# Teensylu-1_3a.net
KiCad netlist of a schematic drawn in EAGLE
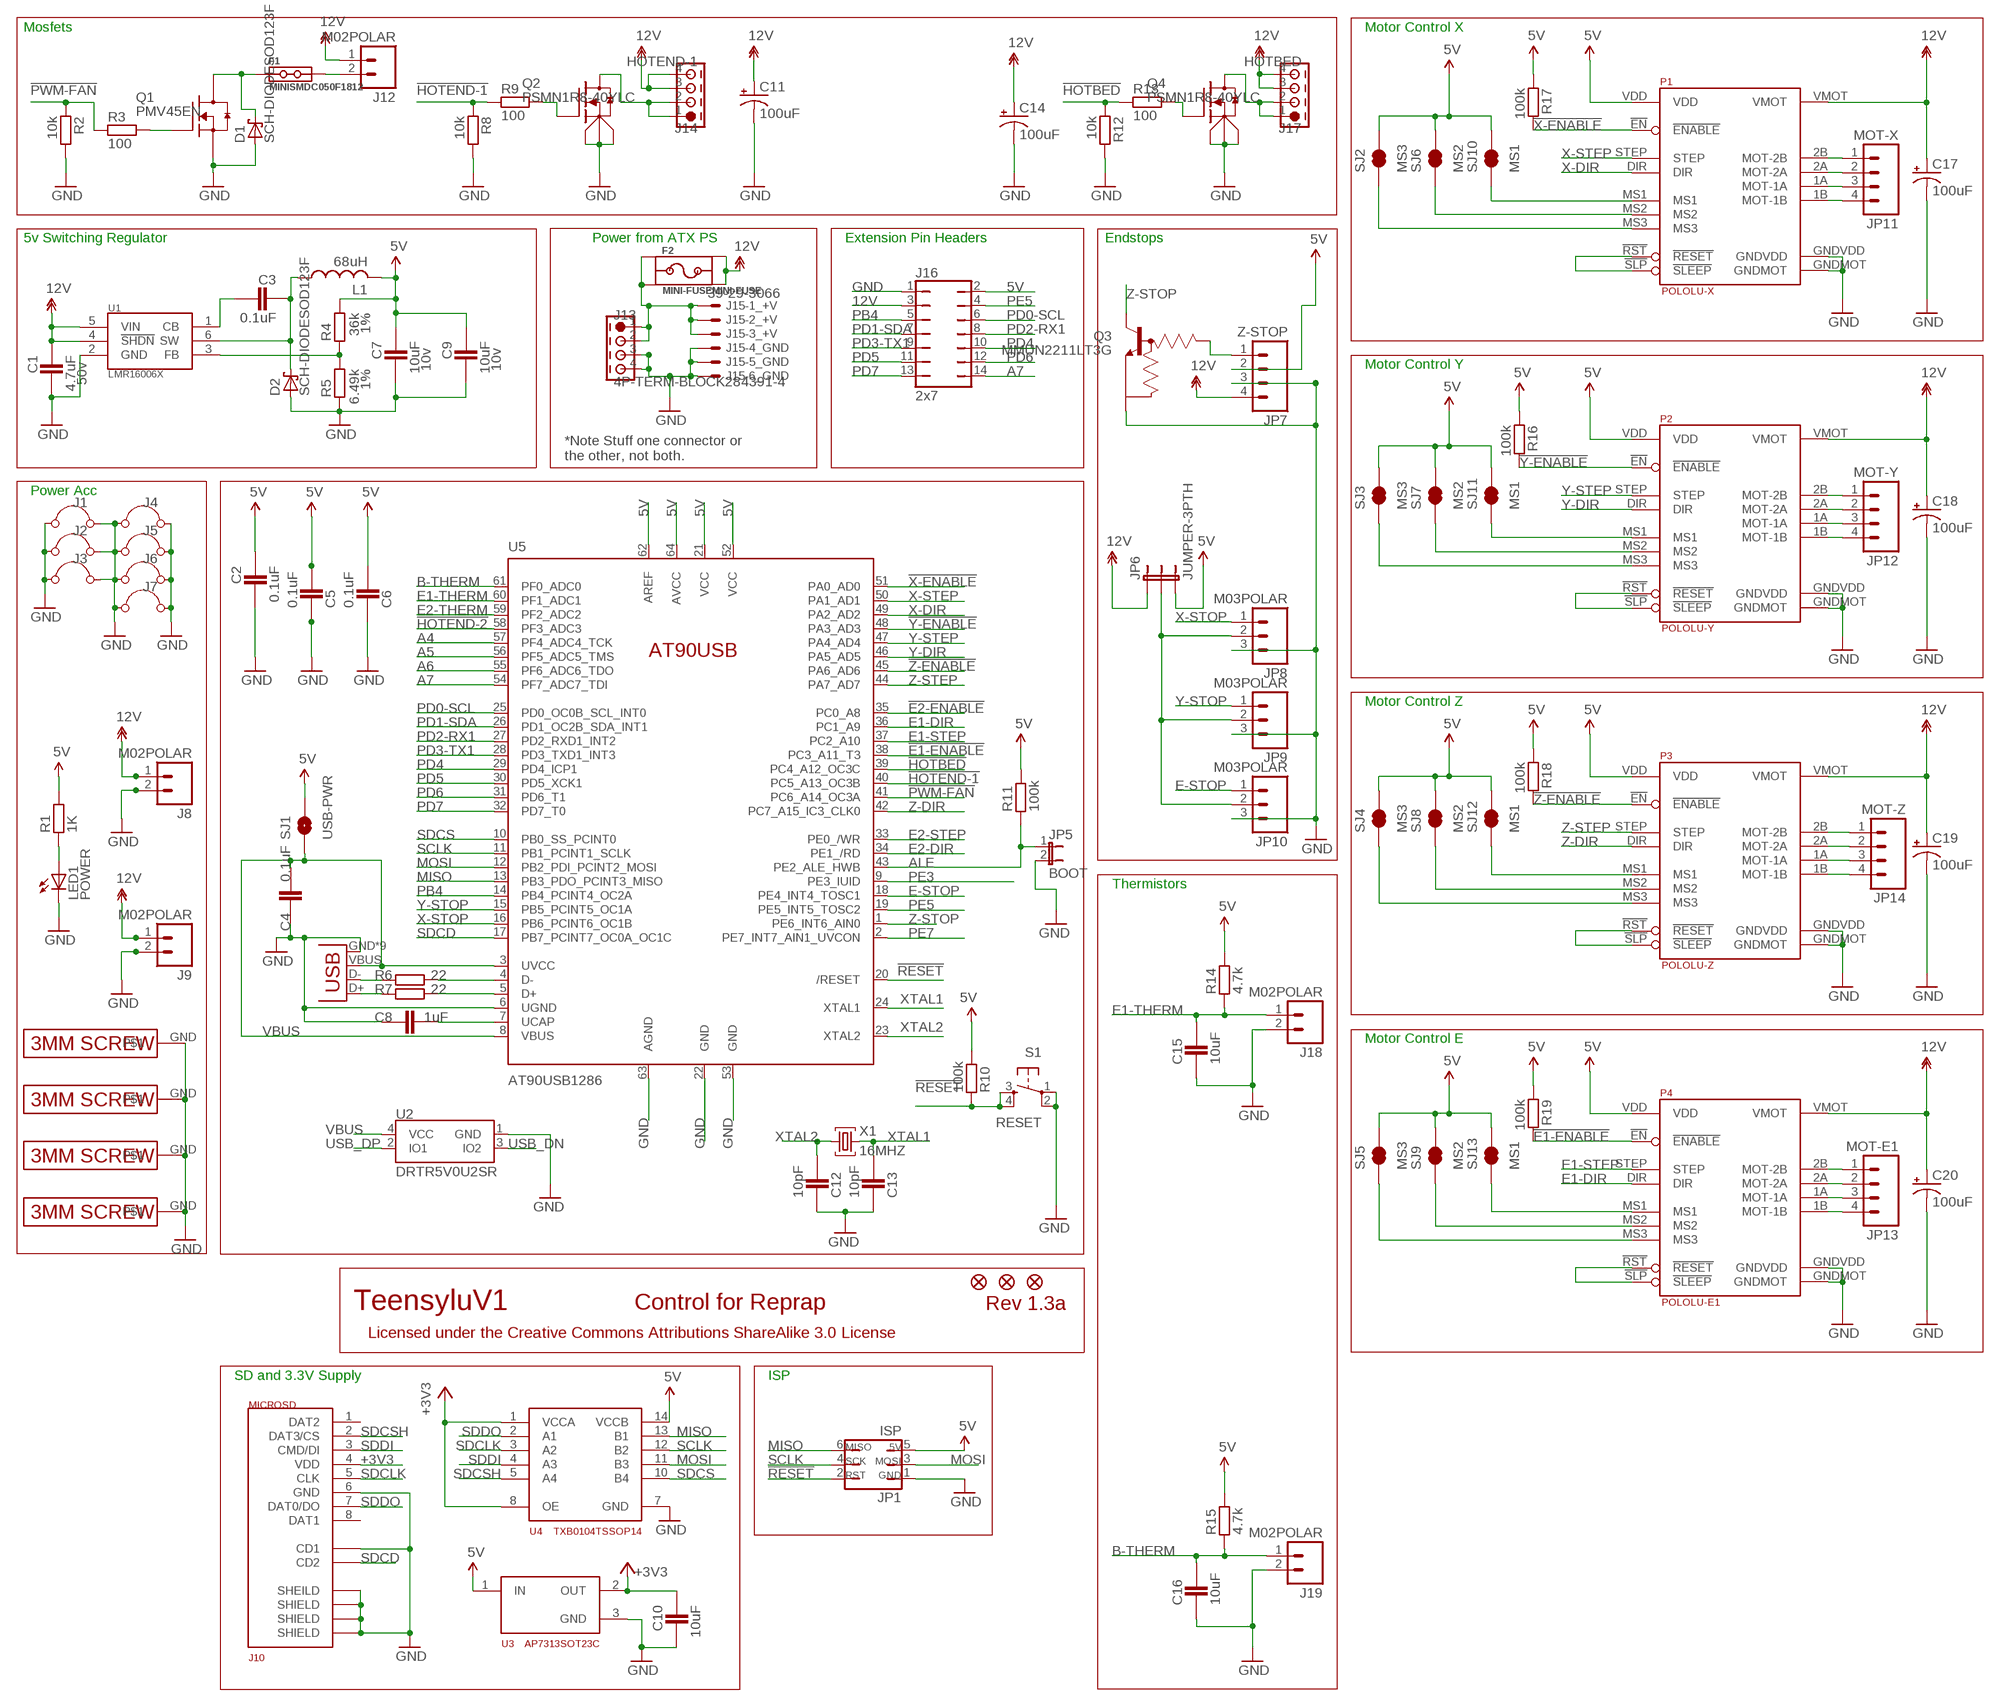
[diagram p0: schematic, sheet 1]

(export (version "E")
  (design (tool "Eeschema 10.0.6"))
  (components
    (comp (ref "C1")
      (value "4.7uF")
      (footprint "eagle-import:CAPC3215X168N")
      (fields
        (field (name "MANUFACTURER") "Yaiyo Yuden")
        (field (name "MANUFACTURER_PART_NUMBER") "UMK316AB7475KL-T")
        (field (name "TOLERANCE") "10%")
        (field (name "VDC") "50v")
      )
      (libsource (lib "eagle-import") (part "CAPACITOR_1206"))
    )
    (comp (ref "C2")
      (value "0.1uF")
      (footprint "eagle-import:CAPC1608X92N")
      (fields
        (field (name "MANUFACTURER") "Murata")
        (field (name "MANUFACTURER_PART_NUMBER") "GRM188R71C104KA01D")
        (field (name "TOLERANCE") "10%")
      )
      (libsource (lib "eagle-import") (part "CAPACITOR_0603"))
    )
    (comp (ref "C3")
      (value "0.1uF")
      (footprint "eagle-import:CAPC1608X92N")
      (fields
        (field (name "MANUFACTURER") "Samsung")
        (field (name "MANUFACTURER_PART_NUMBER") "CL10B104KB8NNNC")
        (field (name "TOLERANCE") "10%")
      )
      (libsource (lib "eagle-import") (part "CAPACITOR_0603"))
    )
    (comp (ref "C4")
      (value "0.1uF")
      (footprint "eagle-import:CAPC1608X92N")
      (fields
        (field (name "MANUFACTURER") "Murata")
        (field (name "MANUFACTURER_PART_NUMBER") "GRM188R71C104KA01D")
        (field (name "TOLERANCE") "10%")
      )
      (libsource (lib "eagle-import") (part "CAPACITOR_0603"))
    )
    (comp (ref "C5")
      (value "0.1uF")
      (footprint "eagle-import:CAPC1608X92N")
      (fields
        (field (name "MANUFACTURER") "Murata")
        (field (name "MANUFACTURER_PART_NUMBER") "GRM188R71C104KA01D")
        (field (name "TOLERANCE") "10%")
      )
      (libsource (lib "eagle-import") (part "CAPACITOR_0603"))
    )
    (comp (ref "C6")
      (value "0.1uF")
      (footprint "eagle-import:CAPC1608X92N")
      (fields
        (field (name "MANUFACTURER") "Murata")
        (field (name "MANUFACTURER_PART_NUMBER") "GRM188R71C104KA01D")
        (field (name "TOLERANCE") "10%")
      )
      (libsource (lib "eagle-import") (part "CAPACITOR_0603"))
    )
    (comp (ref "C7")
      (value "10uF")
      (footprint "eagle-import:CAPC2012X145AN")
      (fields
        (field (name "MANUFACTURER") "Murata")
        (field (name "MANUFACTURER_PART_NUMBER") "GRM21BR71A106KE51L")
        (field (name "TOLERANCE") "10%")
        (field (name "VDC") "10v")
      )
      (libsource (lib "eagle-import") (part "CAPACITOR_0805"))
    )
    (comp (ref "C8")
      (value "1uF")
      (footprint "eagle-import:CAPC1608X92N")
      (fields
        (field (name "MANUFACTURER") "Samsung")
        (field (name "MANUFACTURER_PART_NUMBER") "CL10A105MO8NNNC")
        (field (name "TOLERANCE") "20%")
      )
      (libsource (lib "eagle-import") (part "CAPACITOR_0603"))
    )
    (comp (ref "C9")
      (value "10uF")
      (footprint "eagle-import:CAPC2012X145AN")
      (fields
        (field (name "MANUFACTURER") "Murata")
        (field (name "MANUFACTURER_PART_NUMBER") "GRM21BR71A106KE51L")
        (field (name "TOLERANCE") "10%")
        (field (name "VDC") "10v")
      )
      (libsource (lib "eagle-import") (part "CAPACITOR_0805"))
    )
    (comp (ref "C10")
      (value "10uF")
      (footprint "eagle-import:CAPC1608X92N")
      (fields
        (field (name "MANUFACTURER") "Murata")
        (field (name "MANUFACTURER_PART_NUMBER") "GRM188R61C106MA73D")
        (field (name "TOLERANCE") "20%")
      )
      (libsource (lib "eagle-import") (part "CAPACITOR_0603"))
    )
    (comp (ref "C11")
      (value "100uF")
      (footprint "eagle-import:PANASONIC_D")
      (fields
        (field (name "MANUFACTURER") "Panasonic")
        (field (name "MANUFACTURER_PART_NUMBER") "EEE-FTH101XAP")
        (field (name "TOLERANCE") "20%")
      )
      (libsource (lib "eagle-import") (part "CPOL-USD"))
    )
    (comp (ref "C12")
      (value "10pF")
      (footprint "eagle-import:CAPC1608X92N")
      (fields
        (field (name "MANUFACTURER") "Samsung")
        (field (name "MANUFACTURER_PART_NUMBER") "CL10C100JB8NCNC")
        (field (name "TOLERANCE") "5%")
      )
      (libsource (lib "eagle-import") (part "CAPACITOR_0603"))
    )
    (comp (ref "C13")
      (value "10pF")
      (footprint "eagle-import:CAPC1608X92N")
      (fields
        (field (name "MANUFACTURER") "Samsung")
        (field (name "MANUFACTURER_PART_NUMBER") "CL10C100JB8NCNC")
        (field (name "TOLERANCE") "5%")
      )
      (libsource (lib "eagle-import") (part "CAPACITOR_0603"))
    )
    (comp (ref "C14")
      (value "100uF")
      (footprint "eagle-import:PANASONIC_D")
      (fields
        (field (name "MANUFACTURER") "Panasonic")
        (field (name "MANUFACTURER_PART_NUMBER") "EEE-FTH101XAP")
        (field (name "TOLERANCE") "20%")
      )
      (libsource (lib "eagle-import") (part "CPOL-USD"))
    )
    (comp (ref "C15")
      (value "10uF")
      (footprint "eagle-import:CAPC1608X92N")
      (fields
        (field (name "MANUFACTURER") "Murata")
        (field (name "MANUFACTURER_PART_NUMBER") "GRM188R61C106MA73D")
        (field (name "TOLERANCE") "20%")
      )
      (libsource (lib "eagle-import") (part "CAPACITOR_0603"))
    )
    (comp (ref "C16")
      (value "10uF")
      (footprint "eagle-import:CAPC1608X92N")
      (fields
        (field (name "MANUFACTURER") "Murata")
        (field (name "MANUFACTURER_PART_NUMBER") "GRM188R61C106MA73D")
        (field (name "TOLERANCE") "20%")
      )
      (libsource (lib "eagle-import") (part "CAPACITOR_0603"))
    )
    (comp (ref "C17")
      (value "100uF")
      (footprint "eagle-import:PANASONIC_D")
      (fields
        (field (name "MANUFACTURER") "Panasonic")
        (field (name "MANUFACTURER_PART_NUMBER") "EEE-FTH101XAP")
        (field (name "TOLERANCE") "20%")
      )
      (libsource (lib "eagle-import") (part "CPOL-USD"))
    )
    (comp (ref "C18")
      (value "100uF")
      (footprint "eagle-import:PANASONIC_D")
      (fields
        (field (name "MANUFACTURER") "Panasonic")
        (field (name "MANUFACTURER_PART_NUMBER") "EEE-FTH101XAP")
        (field (name "TOLERANCE") "20%")
      )
      (libsource (lib "eagle-import") (part "CPOL-USD"))
    )
    (comp (ref "C19")
      (value "100uF")
      (footprint "eagle-import:PANASONIC_D")
      (fields
        (field (name "MANUFACTURER") "Panasonic")
        (field (name "MANUFACTURER_PART_NUMBER") "EEE-FTH101XAP")
        (field (name "TOLERANCE") "20%")
      )
      (libsource (lib "eagle-import") (part "CPOL-USD"))
    )
    (comp (ref "C20")
      (value "100uF")
      (footprint "eagle-import:PANASONIC_D")
      (fields
        (field (name "MANUFACTURER") "Panasonic")
        (field (name "MANUFACTURER_PART_NUMBER") "EEE-FTH101XAP")
        (field (name "TOLERANCE") "20%")
      )
      (libsource (lib "eagle-import") (part "CPOL-USD"))
    )
    (comp (ref "D1")
      (value "SCH-DIODESOD123F")
      (footprint "eagle-import:SOD123F")
      (fields
        (field (name "MANUFACTURER") "NXP Semiconductors")
        (field (name "MANUFACTURER_PART_NUMBER") "PMEG4010CEH,115")
        (field (name "CURRENT") "1A")
        (field (name "MANUFACTURER_1") "NXP Semiconductors")
      )
      (libsource (lib "eagle-import") (part "SCH-DIODESOD123F"))
    )
    (comp (ref "D2")
      (value "SCH-DIODESOD123F")
      (footprint "eagle-import:SOD123F")
      (fields
        (field (name "MANUFACTURER") "NXP Semiconductors")
        (field (name "MANUFACTURER_PART_NUMBER") "PMEG4010CEH,115")
        (field (name "CURRENT") "1A")
        (field (name "MANUFACTURER_1") "NXP Semiconductors")
        (field (name "MANUFACTURER_PART_NUMBER_1") "PMEG4010CEH,115")
        (field (name "REVERSE_VOLTAGE") "40V")
      )
      (libsource (lib "eagle-import") (part "SCH-DIODESOD123F"))
    )
    (comp (ref "F1")
      (value "MINISMDC050F1812")
      (footprint "eagle-import:MINISMDC")
      (fields
        (field (name "MANUFACTURER") "TE Connectivity")
        (field (name "MANUFACTURER_PART_NUMBER") "MINISMDC050F-2")
      )
      (libsource (lib "eagle-import") (part "MINISMDC050F1812"))
    )
    (comp (ref "F2")
      (value "MINI-FUSEMINI-FUSE")
      (footprint "eagle-import:MINI_FUSE")
      (fields (field (name "MANUFACTURER") "Keystone") (field (name "MANUFACTURER_PART_NUMBER") "3568"))
      (libsource (lib "eagle-import") (part "MINI-FUSEMINI-FUSE"))
    )
    (comp (ref "J1")
      (value "22ga")
      (footprint "eagle-import:WJ_01_08")
      (description "22ga jumper wire")
      (libsource (lib "eagle-import") (part "WIRE_JUMPER-0.1"))
    )
    (comp (ref "J2")
      (value "22ga")
      (footprint "eagle-import:WJ_01_08")
      (description "22ga jumper wire")
      (libsource (lib "eagle-import") (part "WIRE_JUMPER-0.1"))
    )
    (comp (ref "J3")
      (value "22ga")
      (footprint "eagle-import:WJ_01_08")
      (description "22ga jumper wire")
      (libsource (lib "eagle-import") (part "WIRE_JUMPER-0.1"))
    )
    (comp (ref "J4")
      (value "22ga")
      (footprint "eagle-import:WJ_01_08")
      (description "22ga jumper wire")
      (libsource (lib "eagle-import") (part "WIRE_JUMPER-0.1"))
    )
    (comp (ref "J5")
      (value "22ga")
      (footprint "eagle-import:WJ_01_08")
      (description "22ga jumper wire")
      (libsource (lib "eagle-import") (part "WIRE_JUMPER-0.1"))
    )
    (comp (ref "J6")
      (value "22ga")
      (footprint "eagle-import:WJ_01_08")
      (description "22ga jumper wire")
      (libsource (lib "eagle-import") (part "WIRE_JUMPER-0.1"))
    )
    (comp (ref "J7")
      (value "22ga")
      (footprint "eagle-import:WJ_01_08")
      (description "22ga jumper wire")
      (libsource (lib "eagle-import") (part "WIRE_JUMPER-0.1"))
    )
    (comp (ref "J8")
      (value "M02POLAR")
      (footprint "eagle-import:MOLEX-1X2")
      (description "CONN HEADER 2POS .100 VERT TIN")
      (fields (field (name "MANUFACTURER") "Molex") (field (name "MANUFACTURER_PART_NUMBER") "0022272021"))
      (libsource (lib "eagle-import") (part "M02POLAR"))
    )
    (comp (ref "J9")
      (value "M02POLAR")
      (footprint "eagle-import:MOLEX-1X2")
      (description "CONN HEADER 2POS .100 VERT TIN")
      (fields (field (name "MANUFACTURER") "Molex") (field (name "MANUFACTURER_PART_NUMBER") "0022272021"))
      (libsource (lib "eagle-import") (part "M02POLAR"))
    )
    (comp (ref "J10")
      (value "MICROSD")
      (footprint "eagle-import:AMPHENOL-MICROSD")
      (description "CONN MICRO SD CARD PUSH-PULL R/A")
      (fields
        (field (name "MANUFACTURER") "Amphenol")
        (field (name "MANUFACTURER_PART_NUMBER") "114-00841-68")
      )
      (libsource (lib "eagle-import") (part "MICROSD"))
    )
    (comp (ref "J11")
      (value "USB-MICRO-PTH")
      (footprint "eagle-import:USB-MICROB-PTH")
      (fields (field (name "MANUFACTURER") "FCI") (field (name "MANUFACTURER_PART_NUMBER") "10118194-0001LF"))
      (libsource (lib "eagle-import") (part "USB-MICRO-PTH"))
    )
    (comp (ref "J12")
      (value "M02POLAR")
      (footprint "eagle-import:MOLEX-1X2")
      (description "CONN HEADER 2POS .100 VERT TIN")
      (fields (field (name "MANUFACTURER") "Molex") (field (name "MANUFACTURER_PART_NUMBER") "0022272021"))
      (libsource (lib "eagle-import") (part "M02POLAR"))
    )
    (comp (ref "J13")
      (value "4P-TERM-BLOCK284391-4")
      (footprint "eagle-import:284391-4")
      (fields
        (field (name "MANUFACTURER") "TE Connectivity")
        (field (name "MANUFACTURER_PART_NUMBER") "284391-4")
      )
      (libsource (lib "eagle-import") (part "4P-TERM-BLOCK284391-4"))
    )
    (comp (ref "J14")
      (value "HOTEND-1")
      (footprint "eagle-import:284391-4")
      (fields
        (field (name "MANUFACTURER") "TE Connectivity")
        (field (name "MANUFACTURER_PART_NUMBER") "284391-4")
      )
      (libsource (lib "eagle-import") (part "4P-TERM-BLOCK284391-4"))
    )
    (comp (ref "J15")
      (value "39-29-3066")
      (footprint "eagle-import:39-29-3066")
      (fields (field (name "MANUFACTURER") "Molex") (field (name "MANUFACTURER_PART_NUMBER") "0039293066"))
      (libsource (lib "eagle-import") (part "39-29-3066"))
    )
    (comp (ref "J16")
      (value "2x7")
      (footprint "eagle-import:JP7Q")
      (description "DIL VERTICAL PC TAIL PIN HEADER")
      (fields (field (name "MANUFACTURER") "Harwin") (field (name "MANUFACTURER_PART_NUMBER") "M20-9980746"))
      (libsource (lib "eagle-import") (part "JP7Q"))
    )
    (comp (ref "J17")
      (value "HOTBED")
      (footprint "eagle-import:284391-4")
      (fields
        (field (name "MANUFACTURER") "TE Connectivity")
        (field (name "MANUFACTURER_PART_NUMBER") "284391-4")
      )
      (libsource (lib "eagle-import") (part "4P-TERM-BLOCK284391-4"))
    )
    (comp (ref "J18")
      (value "M02POLAR")
      (footprint "eagle-import:MOLEX-1X2")
      (description "CONN HEADER 2POS .100 VERT TIN")
      (fields (field (name "MANUFACTURER") "Molex") (field (name "MANUFACTURER_PART_NUMBER") "0022272021"))
      (libsource (lib "eagle-import") (part "M02POLAR"))
    )
    (comp (ref "J19")
      (value "M02POLAR")
      (footprint "eagle-import:MOLEX-1X2")
      (description "CONN HEADER 2POS .100 VERT TIN")
      (fields (field (name "MANUFACTURER") "Molex") (field (name "MANUFACTURER_PART_NUMBER") "0022272021"))
      (libsource (lib "eagle-import") (part "M02POLAR"))
    )
    (comp (ref "JP1")
      (value "ISP")
      (footprint "eagle-import:ISP")
      (libsource (lib "eagle-import") (part "PROGHEADER"))
    )
    (comp (ref "JP2")
      (value "FIDUCIAL1X2.5")
      (footprint "eagle-import:FIDUCIAL-1X2.5")
      (libsource (lib "eagle-import") (part "FIDUCIAL1X2.5"))
    )
    (comp (ref "JP3")
      (value "FIDUCIAL1X2.5")
      (footprint "eagle-import:FIDUCIAL-1X2.5")
      (libsource (lib "eagle-import") (part "FIDUCIAL1X2.5"))
    )
    (comp (ref "JP4")
      (value "FIDUCIAL1X2.5")
      (footprint "eagle-import:FIDUCIAL-1X2.5")
      (libsource (lib "eagle-import") (part "FIDUCIAL1X2.5"))
    )
    (comp (ref "JP5")
      (value "BOOT")
      (footprint "eagle-import:1X02")
      (description "SIL VERTICAL PC TAIL PIN HEADER")
      (fields (field (name "MANUFACTURER") "Harwin") (field (name "MANUFACTURER_PART_NUMBER") "M20-9990246"))
      (libsource (lib "eagle-import") (part "JUMPER-2PTH"))
    )
    (comp (ref "JP6")
      (value "JUMPER-3PTH")
      (footprint "eagle-import:1X03")
      (libsource (lib "eagle-import") (part "JUMPER-3PTH"))
    )
    (comp (ref "JP7")
      (value "Z-STOP")
      (footprint "eagle-import:MOLEX-1X4")
      (fields (field (name "MANUFACTURER") "Molex") (field (name "MANUFACTURER_PART_NUMBER") "0022272041"))
      (libsource (lib "eagle-import") (part "M04POLAR"))
    )
    (comp (ref "JP8")
      (value "M03POLAR")
      (footprint "eagle-import:MOLEX-1X3")
      (description "CONN HEADER 3POS .100 VERT TIN")
      (fields (field (name "MANUFACTURER") "Molex") (field (name "MANUFACTURER_PART_NUMBER") "0022272031"))
      (libsource (lib "eagle-import") (part "M03POLAR"))
    )
    (comp (ref "JP9")
      (value "M03POLAR")
      (footprint "eagle-import:MOLEX-1X3")
      (description "CONN HEADER 3POS .100 VERT TIN")
      (fields (field (name "MANUFACTURER") "Molex") (field (name "MANUFACTURER_PART_NUMBER") "0022272031"))
      (libsource (lib "eagle-import") (part "M03POLAR"))
    )
    (comp (ref "JP10")
      (value "M03POLAR")
      (footprint "eagle-import:MOLEX-1X3")
      (description "CONN HEADER 3POS .100 VERT TIN")
      (fields (field (name "MANUFACTURER") "Molex") (field (name "MANUFACTURER_PART_NUMBER") "0022272031"))
      (libsource (lib "eagle-import") (part "M03POLAR"))
    )
    (comp (ref "JP11")
      (value "MOT-X")
      (footprint "eagle-import:MOLEX-1X4")
      (fields (field (name "MANUFACTURER") "Molex") (field (name "MANUFACTURER_PART_NUMBER") "0022272041"))
      (libsource (lib "eagle-import") (part "M04POLAR"))
    )
    (comp (ref "JP12")
      (value "MOT-Y")
      (footprint "eagle-import:MOLEX-1X4")
      (fields (field (name "MANUFACTURER") "Molex") (field (name "MANUFACTURER_PART_NUMBER") "0022272041"))
      (libsource (lib "eagle-import") (part "M04POLAR"))
    )
    (comp (ref "JP13")
      (value "MOT-E1")
      (footprint "eagle-import:MOLEX-1X4")
      (fields (field (name "MANUFACTURER") "Molex") (field (name "MANUFACTURER_PART_NUMBER") "0022272041"))
      (libsource (lib "eagle-import") (part "M04POLAR"))
    )
    (comp (ref "JP14")
      (value "MOT-Z")
      (footprint "eagle-import:MOLEX-1X4")
      (fields (field (name "MANUFACTURER") "Molex") (field (name "MANUFACTURER_PART_NUMBER") "0022272041"))
      (libsource (lib "eagle-import") (part "M04POLAR"))
    )
    (comp (ref "L1")
      (value "68uH")
      (footprint "eagle-import:SRN6045")
      (fields
        (field (name "MANUFACTURER") "Bourns")
        (field (name "MANUFACTURER_PART_NUMBER") "SRN6045-680M")
        (field (name "MANUFACTURER_1") "Bourns")
        (field (name "MANUFACTURER_PART_NUMBER_1") "SRN6045-680M")
      )
      (libsource (lib "eagle-import") (part "INDUCTORSRN6045"))
    )
    (comp (ref "LED1")
      (value "POWER")
      (footprint "eagle-import:CHIPLED_0805")
      (fields
        (field (name "MANUFACTURER") "Kingbright")
        (field (name "MANUFACTURER_PART_NUMBER") "APT2012SGC")
      )
      (libsource (lib "eagle-import") (part "LEDCHIPLED_0805"))
    )
    (comp (ref "P1")
      (value "POLOLU-X")
      (footprint "eagle-import:POLOLU-STEPPER-PTH")
      (libsource (lib "eagle-import") (part "POLOLU-ALLEGRO"))
    )
    (comp (ref "P2")
      (value "POLOLU-Y")
      (footprint "eagle-import:POLOLU-STEPPER-PTH")
      (libsource (lib "eagle-import") (part "POLOLU-ALLEGRO"))
    )
    (comp (ref "P3")
      (value "POLOLU-Z")
      (footprint "eagle-import:POLOLU-STEPPER-PTH")
      (libsource (lib "eagle-import") (part "POLOLU-ALLEGRO"))
    )
    (comp (ref "P4")
      (value "POLOLU-E1")
      (footprint "eagle-import:POLOLU-STEPPER-PTH")
      (libsource (lib "eagle-import") (part "POLOLU-ALLEGRO"))
    )
    (comp (ref "Q1")
      (value "PMV45EN")
      (footprint "eagle-import:SOT23C")
      (fields
        (field (name "MANUFACTURER") "International Rectifier")
        (field (name "MANUFACTURER_PART_NUMBER") "IRLML2060TRPBF")
        (field (name "VOLTAGE") "60V")
      )
      (libsource (lib "eagle-import") (part "MOSFET-NCH_SOT-23"))
    )
    (comp (ref "Q2")
      (value "PSMN1R8-40YLC")
      (footprint "eagle-import:LFPACK-POWERPAK-SO8")
      (fields
        (field (name "MANUFACTURER") "NXP Semiconductors")
        (field (name "MANUFACTURER_PART_NUMBER") "PSMN1R8-40YLC,115")
        (field (name "VOLTAGE") "40V")
      )
      (libsource (lib "eagle-import") (part "PSMN1R8-40YLCPOWERPACK-S08"))
    )
    (comp (ref "Q3")
      (value "MMUN2211LT3G")
      (footprint "eagle-import:SOT23C")
      (description "TRANS PREBIAS NPN 246MW SOT23-3")
      (fields (field (name "MANUFACTURER") "ON Semiconductor"))
      (libsource (lib "eagle-import") (part "TRANSISTOR_NPN_BIASSOT23C"))
    )
    (comp (ref "Q4")
      (value "PSMN1R8-40YLC")
      (footprint "eagle-import:LFPACK-POWERPAK-SO8")
      (fields
        (field (name "MANUFACTURER") "NXP Semiconductors")
        (field (name "MANUFACTURER_PART_NUMBER") "PSMN1R8-40YLC,115")
        (field (name "VOLTAGE") "40V")
      )
      (libsource (lib "eagle-import") (part "PSMN1R8-40YLCPOWERPACK-S08"))
    )
    (comp (ref "R1")
      (value "1K")
      (footprint "eagle-import:RESC1608X55N")
      (libsource (lib "eagle-import") (part "RESISTOR_0603"))
    )
    (comp (ref "R2")
      (value "10k")
      (footprint "eagle-import:RESC1608X55N")
      (libsource (lib "eagle-import") (part "RESISTOR_0603"))
    )
    (comp (ref "R3")
      (value "100")
      (footprint "eagle-import:RESC1608X55N")
      (libsource (lib "eagle-import") (part "RESISTOR_0603"))
    )
    (comp (ref "R4")
      (value "36k")
      (footprint "eagle-import:RESC1608X55N")
      (fields (field (name "TOLERANCE") "1%"))
      (libsource (lib "eagle-import") (part "RESISTOR_0603"))
    )
    (comp (ref "R5")
      (value "6.49k")
      (footprint "eagle-import:RESC1608X55N")
      (fields (field (name "TOLERANCE") "1%"))
      (libsource (lib "eagle-import") (part "RESISTOR_0603"))
    )
    (comp (ref "R6")
      (value "22")
      (footprint "eagle-import:RESC1608X55N")
      (libsource (lib "eagle-import") (part "RESISTOR_0603"))
    )
    (comp (ref "R7")
      (value "22")
      (footprint "eagle-import:RESC1608X55N")
      (libsource (lib "eagle-import") (part "RESISTOR_0603"))
    )
    (comp (ref "R8")
      (value "10k")
      (footprint "eagle-import:RESC1608X55N")
      (libsource (lib "eagle-import") (part "RESISTOR_0603"))
    )
    (comp (ref "R9")
      (value "100")
      (footprint "eagle-import:RESC1608X55N")
      (libsource (lib "eagle-import") (part "RESISTOR_0603"))
    )
    (comp (ref "R10")
      (value "100k")
      (footprint "eagle-import:RESC1608X55N")
      (libsource (lib "eagle-import") (part "RESISTOR_0603"))
    )
    (comp (ref "R11")
      (value "100k")
      (footprint "eagle-import:RESC1608X55N")
      (libsource (lib "eagle-import") (part "RESISTOR_0603"))
    )
    (comp (ref "R12")
      (value "10k")
      (footprint "eagle-import:RESC1608X55N")
      (libsource (lib "eagle-import") (part "RESISTOR_0603"))
    )
    (comp (ref "R13")
      (value "100")
      (footprint "eagle-import:RESC1608X55N")
      (libsource (lib "eagle-import") (part "RESISTOR_0603"))
    )
    (comp (ref "R14")
      (value "4.7k")
      (footprint "eagle-import:RESC1608X55N")
      (libsource (lib "eagle-import") (part "RESISTOR_0603"))
    )
    (comp (ref "R15")
      (value "4.7k")
      (footprint "eagle-import:RESC1608X55N")
      (libsource (lib "eagle-import") (part "RESISTOR_0603"))
    )
    (comp (ref "R16")
      (value "100k")
      (footprint "eagle-import:RESC1608X55N")
      (libsource (lib "eagle-import") (part "RESISTOR_0603"))
    )
    (comp (ref "R17")
      (value "100k")
      (footprint "eagle-import:RESC1608X55N")
      (libsource (lib "eagle-import") (part "RESISTOR_0603"))
    )
    (comp (ref "R18")
      (value "100k")
      (footprint "eagle-import:RESC1608X55N")
      (libsource (lib "eagle-import") (part "RESISTOR_0603"))
    )
    (comp (ref "R19")
      (value "100k")
      (footprint "eagle-import:RESC1608X55N")
      (libsource (lib "eagle-import") (part "RESISTOR_0603"))
    )
    (comp (ref "S1")
      (value "RESET")
      (footprint "eagle-import:TACTILE_SWITCH_SMD")
      (fields (field (name "MANUFACTURER") "Bourns") (field (name "MANUFACTURER_PART_NUMBER") "7914J-1-000E"))
      (libsource (lib "eagle-import") (part "TAC_SWITCHSMD"))
    )
    (comp (ref "SCREW1")
      (value "3MM-SCREW")
      (footprint "eagle-import:PLATEDSCREW")
      (libsource (lib "eagle-import") (part "3MM-SCREW"))
    )
    (comp (ref "SCREW2")
      (value "3MM-SCREW")
      (footprint "eagle-import:PLATEDSCREW")
      (libsource (lib "eagle-import") (part "3MM-SCREW"))
    )
    (comp (ref "SCREW3")
      (value "3MM-SCREW")
      (footprint "eagle-import:PLATEDSCREW")
      (libsource (lib "eagle-import") (part "3MM-SCREW"))
    )
    (comp (ref "SCREW4")
      (value "3MM-SCREW")
      (footprint "eagle-import:PLATEDSCREW")
      (libsource (lib "eagle-import") (part "3MM-SCREW"))
    )
    (comp (ref "SJ1")
      (value "USB-PWR")
      (footprint "eagle-import:SJ_2S-NO")
      (libsource (lib "eagle-import") (part "SOLDERJUMPERNO"))
    )
    (comp (ref "SJ2")
      (value "MS3")
      (footprint "eagle-import:SJ_2S-TRACE")
      (libsource (lib "eagle-import") (part "SOLDERJUMPER-NCSJ-TRACE"))
    )
    (comp (ref "SJ3")
      (value "MS3")
      (footprint "eagle-import:SJ_2S-TRACE")
      (libsource (lib "eagle-import") (part "SOLDERJUMPER-NCSJ-TRACE"))
    )
    (comp (ref "SJ4")
      (value "MS3")
      (footprint "eagle-import:SJ_2S-TRACE")
      (libsource (lib "eagle-import") (part "SOLDERJUMPER-NCSJ-TRACE"))
    )
    (comp (ref "SJ5")
      (value "MS3")
      (footprint "eagle-import:SJ_2S-TRACE")
      (libsource (lib "eagle-import") (part "SOLDERJUMPER-NCSJ-TRACE"))
    )
    (comp (ref "SJ6")
      (value "MS2")
      (footprint "eagle-import:SJ_2S-TRACE")
      (libsource (lib "eagle-import") (part "SOLDERJUMPER-NCSJ-TRACE"))
    )
    (comp (ref "SJ7")
      (value "MS2")
      (footprint "eagle-import:SJ_2S-TRACE")
      (libsource (lib "eagle-import") (part "SOLDERJUMPER-NCSJ-TRACE"))
    )
    (comp (ref "SJ8")
      (value "MS2")
      (footprint "eagle-import:SJ_2S-TRACE")
      (libsource (lib "eagle-import") (part "SOLDERJUMPER-NCSJ-TRACE"))
    )
    (comp (ref "SJ9")
      (value "MS2")
      (footprint "eagle-import:SJ_2S-TRACE")
      (libsource (lib "eagle-import") (part "SOLDERJUMPER-NCSJ-TRACE"))
    )
    (comp (ref "SJ10")
      (value "MS1")
      (footprint "eagle-import:SJ_2S-TRACE")
      (libsource (lib "eagle-import") (part "SOLDERJUMPER-NCSJ-TRACE"))
    )
    (comp (ref "SJ11")
      (value "MS1")
      (footprint "eagle-import:SJ_2S-TRACE")
      (libsource (lib "eagle-import") (part "SOLDERJUMPER-NCSJ-TRACE"))
    )
    (comp (ref "SJ12")
      (value "MS1")
      (footprint "eagle-import:SJ_2S-TRACE")
      (libsource (lib "eagle-import") (part "SOLDERJUMPER-NCSJ-TRACE"))
    )
    (comp (ref "SJ13")
      (value "MS1")
      (footprint "eagle-import:SJ_2S-TRACE")
      (libsource (lib "eagle-import") (part "SOLDERJUMPER-NCSJ-TRACE"))
    )
    (comp (ref "U1")
      (value "LMR16006X")
      (footprint "eagle-import:TSOT6")
      (fields
        (field (name "MANUFACTURER") "Texas Instruments")
        (field (name "MANUFACTURER_PART_NUMBER") "LMR16006XDDCT")
      )
      (libsource (lib "eagle-import") (part "LMR16006X"))
    )
    (comp (ref "U2")
      (value "DRTR5V0U2SR")
      (footprint "eagle-import:SOT143-R")
      (fields
        (field (name "MANUFACTURER") "Diodes Incorporated")
        (field (name "MANUFACTURER_PART_NUMBER") "DTR5V0U2SR")
      )
      (libsource (lib "eagle-import") (part "DRTR5V0U2SR"))
    )
    (comp (ref "U3")
      (value "AP7313SOT23C")
      (footprint "eagle-import:SOT23C")
      (description "IC REG LDO 3.3V 0.15A SOT23-3")
      (fields
        (field (name "MANUFACTURER") "Diodes Incorporated")
        (field (name "MANUFACTURER_PART_NUMBER") "AP7313-33SAG-7")
      )
      (libsource (lib "eagle-import") (part "AP7313SOT23C"))
    )
    (comp (ref "U4")
      (value "TXB0104TSSOP14")
      (footprint "eagle-import:TSSOP14")
      (description "IC VOLT-LEVEL TRANSLATOR 14TSSOP")
      (fields
        (field (name "MANUFACTURER") "Texas Instruments")
        (field (name "MANUFACTURER_PART_NUMBER") "TXB0104PWR")
      )
      (libsource (lib "eagle-import") (part "TXB0104TSSOP14"))
    )
    (comp (ref "U5")
      (value "AT90USB1286")
      (footprint "eagle-import:TQFP64-2")
      (fields (field (name "MANUFACTURER") "Atmel"))
      (libsource (lib "eagle-import") (part "AT90USB"))
    )
    (comp (ref "X1")
      (value "16MHZ")
      (footprint "eagle-import:NDK-XTAL")
      (fields
        (field (name "MANUFACTURER") "NDK")
        (field (name "MANUFACTURER_PART_NUMBER") "NX5032GA-16.000000MHZ-LN-CD-1")
      )
      (libsource (lib "eagle-import") (part "XTAL"))
    )
  )
  (nets
    (net (code "1") (name "+3V3") (class "Default")
      (node (ref "C10") (pin "1") (pinfunction "1_1") (pintype "passive"))
      (node (ref "J10") (pin "4") (pinfunction "VDD_4") (pintype "power_in"))
      (node (ref "U3") (pin "2") (pinfunction "OUT_2") (pintype "power_in"))
      (node (ref "U4") (pin "1") (pinfunction "VCCA_1") (pintype "power_in"))
      (node (ref "U4") (pin "8") (pinfunction "OE_8") (pintype "input"))
    )
    (net (code "2") (name "/A4") (class "Default")
      (node (ref "U5") (pin "57") (pinfunction "PF4_ADC4_TCK_57") (pintype "bidirectional"))
    )
    (net (code "3") (name "/A5") (class "Default")
      (node (ref "U5") (pin "56") (pinfunction "PF5_ADC5_TMS_56") (pintype "bidirectional"))
    )
    (net (code "4") (name "/A6") (class "Default")
      (node (ref "U5") (pin "55") (pinfunction "PF6_ADC6_TDO_55") (pintype "bidirectional"))
    )
    (net (code "5") (name "/A7") (class "Default")
      (node (ref "J16") (pin "14") (pinfunction "14_14") (pintype "passive"))
      (node (ref "U5") (pin "54") (pinfunction "PF7_ADC7_TDI_54") (pintype "bidirectional"))
    )
    (net (code "6") (name "/ALE") (class "Default")
      (node (ref "JP5") (pin "1") (pinfunction "1_1") (pintype "passive"))
      (node (ref "R11") (pin "1") (pinfunction "1_1") (pintype "passive"))
      (node (ref "U5") (pin "43") (pinfunction "PE2_ALE_HWB_43") (pintype "bidirectional"))
    )
    (net (code "7") (name "/B-THERM") (class "Default")
      (node (ref "C16") (pin "2") (pinfunction "2_2") (pintype "passive"))
      (node (ref "J19") (pin "1") (pinfunction "1_1") (pintype "passive"))
      (node (ref "R15") (pin "1") (pinfunction "1_1") (pintype "passive"))
      (node (ref "U5") (pin "61") (pinfunction "PF0_ADC0_61") (pintype "bidirectional"))
    )
    (net (code "8") (name "/E-STOP") (class "Default")
      (node (ref "JP10") (pin "1") (pinfunction "1_1") (pintype "passive"))
      (node (ref "U5") (pin "18") (pinfunction "PE4_INT4_TOSC1_18") (pintype "bidirectional"))
    )
    (net (code "9") (name "/E1-DIR") (class "Default")
      (node (ref "P4") (pin "DIR") (pinfunction "DIR_DIR") (pintype "bidirectional"))
      (node (ref "U5") (pin "36") (pinfunction "PC1_A9_36") (pintype "bidirectional"))
    )
    (net (code "10") (name "/E1-STEP") (class "Default")
      (node (ref "P4") (pin "STEP") (pinfunction "STEP_STEP") (pintype "bidirectional"))
      (node (ref "U5") (pin "37") (pinfunction "PC2_A10_37") (pintype "bidirectional"))
    )
    (net (code "11") (name "/E1-THERM") (class "Default")
      (node (ref "C15") (pin "2") (pinfunction "2_2") (pintype "passive"))
      (node (ref "J18") (pin "1") (pinfunction "1_1") (pintype "passive"))
      (node (ref "R14") (pin "1") (pinfunction "1_1") (pintype "passive"))
      (node (ref "U5") (pin "60") (pinfunction "PF1_ADC1_60") (pintype "bidirectional"))
    )
    (net (code "12") (name "/E2-DIR") (class "Default")
      (node (ref "U5") (pin "34") (pinfunction "PE1_/RD_34") (pintype "bidirectional"))
    )
    (net (code "13") (name "/E2-STEP") (class "Default")
      (node (ref "U5") (pin "33") (pinfunction "PE0_/WR_33") (pintype "bidirectional"))
    )
    (net (code "14") (name "/E2-THERM") (class "Default")
      (node (ref "U5") (pin "59") (pinfunction "PF2_ADC2_59") (pintype "bidirectional"))
    )
    (net (code "15") (name "/MISO") (class "Default")
      (node (ref "JP1") (pin "6") (pinfunction "6_6") (pintype "passive"))
      (node (ref "U4") (pin "13") (pinfunction "B1_13") (pintype "bidirectional"))
      (node (ref "U5") (pin "13") (pinfunction "PB3_PDO_PCINT3_MISO_13") (pintype "bidirectional"))
    )
    (net (code "16") (name "/MOSI") (class "Default")
      (node (ref "JP1") (pin "3") (pinfunction "3_3") (pintype "passive"))
      (node (ref "U4") (pin "11") (pinfunction "B3_11") (pintype "bidirectional"))
      (node (ref "U5") (pin "12") (pinfunction "PB2_PDI_PCINT2_MOSI_12") (pintype "bidirectional"))
    )
    (net (code "17") (name "/PB4") (class "Default")
      (node (ref "J16") (pin "5") (pinfunction "5_5") (pintype "passive"))
      (node (ref "U5") (pin "14") (pinfunction "PB4_PCINT4_OC2A_14") (pintype "bidirectional"))
    )
    (net (code "18") (name "/PD0-SCL") (class "Default")
      (node (ref "J16") (pin "6") (pinfunction "6_6") (pintype "passive"))
      (node (ref "U5") (pin "25") (pinfunction "PD0_OC0B_SCL_INT0_25") (pintype "bidirectional"))
    )
    (net (code "19") (name "/PD1-SDA") (class "Default")
      (node (ref "J16") (pin "7") (pinfunction "7_7") (pintype "passive"))
      (node (ref "U5") (pin "26") (pinfunction "PD1_OC2B_SDA_INT1_26") (pintype "bidirectional"))
    )
    (net (code "20") (name "/PD2-RX1") (class "Default")
      (node (ref "J16") (pin "8") (pinfunction "8_8") (pintype "passive"))
      (node (ref "U5") (pin "27") (pinfunction "PD2_RXD1_INT2_27") (pintype "bidirectional"))
    )
    (net (code "21") (name "/PD3-TX1") (class "Default")
      (node (ref "J16") (pin "9") (pinfunction "9_9") (pintype "passive"))
      (node (ref "U5") (pin "28") (pinfunction "PD3_TXD1_INT3_28") (pintype "bidirectional"))
    )
    (net (code "22") (name "/PD4") (class "Default")
      (node (ref "J16") (pin "10") (pinfunction "10_10") (pintype "passive"))
      (node (ref "U5") (pin "29") (pinfunction "PD4_ICP1_29") (pintype "bidirectional"))
    )
    (net (code "23") (name "/PD5") (class "Default")
      (node (ref "J16") (pin "11") (pinfunction "11_11") (pintype "passive"))
      (node (ref "U5") (pin "30") (pinfunction "PD5_XCK1_30") (pintype "bidirectional"))
    )
    (net (code "24") (name "/PD6") (class "Default")
      (node (ref "J16") (pin "12") (pinfunction "12_12") (pintype "passive"))
      (node (ref "U5") (pin "31") (pinfunction "PD6_T1_31") (pintype "bidirectional"))
    )
    (net (code "25") (name "/PD7") (class "Default")
      (node (ref "J16") (pin "13") (pinfunction "13_13") (pintype "passive"))
      (node (ref "U5") (pin "32") (pinfunction "PD7_T0_32") (pintype "bidirectional"))
    )
    (net (code "26") (name "/PE3") (class "Default")
      (node (ref "U5") (pin "9") (pinfunction "PE3_IUID_9") (pintype "bidirectional"))
    )
    (net (code "27") (name "/PE5") (class "Default")
      (node (ref "J16") (pin "4") (pinfunction "4_4") (pintype "passive"))
      (node (ref "U5") (pin "19") (pinfunction "PE5_INT5_TOSC2_19") (pintype "bidirectional"))
    )
    (net (code "28") (name "/PE7") (class "Default")
      (node (ref "U5") (pin "2") (pinfunction "PE7_INT7_AIN1_UVCON_2") (pintype "bidirectional"))
    )
    (net (code "29") (name "/SCLK") (class "Default")
      (node (ref "JP1") (pin "4") (pinfunction "4_4") (pintype "passive"))
      (node (ref "U4") (pin "12") (pinfunction "B2_12") (pintype "bidirectional"))
      (node (ref "U5") (pin "11") (pinfunction "PB1_PCINT1_SCLK_11") (pintype "bidirectional"))
    )
    (net (code "30") (name "/SDCD") (class "Default")
      (node (ref "J10") (pin "CD2") (pinfunction "CD2_CD2") (pintype "bidirectional"))
      (node (ref "U5") (pin "17") (pinfunction "PB7_PCINT7_OC0A_OC1C_17") (pintype "bidirectional"))
    )
    (net (code "31") (name "/SDCLK") (class "Default")
      (node (ref "J10") (pin "5") (pinfunction "CLK_5") (pintype "input"))
      (node (ref "U4") (pin "3") (pinfunction "A2_3") (pintype "bidirectional"))
    )
    (net (code "32") (name "/SDCS") (class "Default")
      (node (ref "U4") (pin "10") (pinfunction "B4_10") (pintype "bidirectional"))
      (node (ref "U5") (pin "10") (pinfunction "PB0_SS_PCINT0_10") (pintype "bidirectional"))
    )
    (net (code "33") (name "/SDCSH") (class "Default")
      (node (ref "J10") (pin "2") (pinfunction "DAT3/CS_2") (pintype "bidirectional"))
      (node (ref "U4") (pin "5") (pinfunction "A4_5") (pintype "bidirectional"))
    )
    (net (code "34") (name "/SDDI") (class "Default")
      (node (ref "J10") (pin "3") (pinfunction "CMD/DI_3") (pintype "input"))
      (node (ref "U4") (pin "4") (pinfunction "A3_4") (pintype "bidirectional"))
    )
    (net (code "35") (name "/SDDO") (class "Default")
      (node (ref "J10") (pin "7") (pinfunction "DAT0/DO_7") (pintype "bidirectional"))
      (node (ref "U4") (pin "2") (pinfunction "A1_2") (pintype "bidirectional"))
    )
    (net (code "36") (name "/USB_DN") (class "Default")
      (node (ref "J11") (pin "D-") (pinfunction "D-_D-") (pintype "bidirectional"))
      (node (ref "R6") (pin "1") (pinfunction "1_1") (pintype "passive"))
      (node (ref "U2") (pin "3") (pinfunction "IO2_3") (pintype "bidirectional"))
    )
    (net (code "37") (name "/USB_DP") (class "Default")
      (node (ref "J11") (pin "D+") (pinfunction "D+_D+") (pintype "bidirectional"))
      (node (ref "R7") (pin "1") (pinfunction "1_1") (pintype "passive"))
      (node (ref "U2") (pin "2") (pinfunction "IO1_2") (pintype "bidirectional"))
    )
    (net (code "38") (name "/VBUS") (class "Default")
      (node (ref "C4") (pin "2") (pinfunction "2_2") (pintype "passive"))
      (node (ref "J11") (pin "VBUS") (pinfunction "VBUS_VBUS") (pintype "bidirectional"))
      (node (ref "SJ1") (pin "1") (pinfunction "1_1") (pintype "passive"))
      (node (ref "U2") (pin "4") (pinfunction "VCC_4") (pintype "power_in"))
      (node (ref "U5") (pin "3") (pinfunction "UVCC_3") (pintype "power_in"))
      (node (ref "U5") (pin "8") (pinfunction "VBUS_8") (pintype "bidirectional"))
    )
    (net (code "39") (name "/X-DIR") (class "Default")
      (node (ref "P1") (pin "DIR") (pinfunction "DIR_DIR") (pintype "bidirectional"))
      (node (ref "U5") (pin "49") (pinfunction "PA2_AD2_49") (pintype "bidirectional"))
    )
    (net (code "40") (name "/X-STEP") (class "Default")
      (node (ref "P1") (pin "STEP") (pinfunction "STEP_STEP") (pintype "bidirectional"))
      (node (ref "U5") (pin "50") (pinfunction "PA1_AD1_50") (pintype "bidirectional"))
    )
    (net (code "41") (name "/X-STOP") (class "Default")
      (node (ref "JP8") (pin "1") (pinfunction "1_1") (pintype "passive"))
      (node (ref "U5") (pin "16") (pinfunction "PB6_PCINT6_OC1B_16") (pintype "bidirectional"))
    )
    (net (code "42") (name "/XTAL1") (class "Default")
      (node (ref "C13") (pin "2") (pinfunction "2_2") (pintype "passive"))
      (node (ref "U5") (pin "24") (pinfunction "XTAL1_24") (pintype "passive"))
      (node (ref "X1") (pin "P$2") (pinfunction "2_P$2") (pintype "passive"))
    )
    (net (code "43") (name "/XTAL2") (class "Default")
      (node (ref "C12") (pin "2") (pinfunction "2_2") (pintype "passive"))
      (node (ref "U5") (pin "23") (pinfunction "XTAL2_23") (pintype "passive"))
      (node (ref "X1") (pin "P$1") (pinfunction "1_P$1") (pintype "passive"))
    )
    (net (code "44") (name "/Y-DIR") (class "Default")
      (node (ref "P2") (pin "DIR") (pinfunction "DIR_DIR") (pintype "bidirectional"))
      (node (ref "U5") (pin "46") (pinfunction "PA5_AD5_46") (pintype "bidirectional"))
    )
    (net (code "45") (name "/Y-STEP") (class "Default")
      (node (ref "P2") (pin "STEP") (pinfunction "STEP_STEP") (pintype "bidirectional"))
      (node (ref "U5") (pin "47") (pinfunction "PA4_AD4_47") (pintype "bidirectional"))
    )
    (net (code "46") (name "/Y-STOP") (class "Default")
      (node (ref "JP9") (pin "1") (pinfunction "1_1") (pintype "passive"))
      (node (ref "U5") (pin "15") (pinfunction "PB5_PCINT5_OC1A_15") (pintype "bidirectional"))
    )
    (net (code "47") (name "/Z-DIR") (class "Default")
      (node (ref "P3") (pin "DIR") (pinfunction "DIR_DIR") (pintype "bidirectional"))
      (node (ref "U5") (pin "42") (pinfunction "PC7_A15_IC3_CLK0_42") (pintype "bidirectional"))
    )
    (net (code "48") (name "/Z-STEP") (class "Default")
      (node (ref "P3") (pin "STEP") (pinfunction "STEP_STEP") (pintype "bidirectional"))
      (node (ref "U5") (pin "44") (pinfunction "PA7_AD7_44") (pintype "bidirectional"))
    )
    (net (code "49") (name "/Z-STOP") (class "Default")
      (node (ref "Q3") (pin "3") (pinfunction "C_3") (pintype "passive"))
      (node (ref "U5") (pin "1") (pinfunction "PE6_INT6_AIN0_1") (pintype "bidirectional"))
    )
    (net (code "50") (name "/~{E1-ENABLE}") (class "Default")
      (node (ref "P4") (pin "!EN") (pinfunction "~{ENABLE}_!EN") (pintype "input"))
      (node (ref "R19") (pin "2") (pinfunction "2_2") (pintype "passive"))
      (node (ref "U5") (pin "38") (pinfunction "PC3_A11_T3_38") (pintype "bidirectional"))
    )
    (net (code "51") (name "/~{E2-ENABLE}") (class "Default")
      (node (ref "U5") (pin "35") (pinfunction "PC0_A8_35") (pintype "bidirectional"))
    )
    (net (code "52") (name "/~{HOTBED}") (class "Default")
      (node (ref "R12") (pin "1") (pinfunction "1_1") (pintype "passive"))
      (node (ref "R13") (pin "1") (pinfunction "1_1") (pintype "passive"))
      (node (ref "U5") (pin "39") (pinfunction "PC4_A12_OC3C_39") (pintype "bidirectional"))
    )
    (net (code "53") (name "/~{HOTEND-1}") (class "Default")
      (node (ref "R8") (pin "1") (pinfunction "1_1") (pintype "passive"))
      (node (ref "R9") (pin "1") (pinfunction "1_1") (pintype "passive"))
      (node (ref "U5") (pin "40") (pinfunction "PC5_A13_OC3B_40") (pintype "bidirectional"))
    )
    (net (code "54") (name "/~{HOTEND-2}") (class "Default")
      (node (ref "U5") (pin "58") (pinfunction "PF3_ADC3_58") (pintype "bidirectional"))
    )
    (net (code "55") (name "/~{PWM-FAN}") (class "Default")
      (node (ref "R2") (pin "1") (pinfunction "1_1") (pintype "passive"))
      (node (ref "R3") (pin "1") (pinfunction "1_1") (pintype "passive"))
      (node (ref "U5") (pin "41") (pinfunction "PC6_A14_OC3A_41") (pintype "bidirectional"))
    )
    (net (code "56") (name "/~{RESET}") (class "Default")
      (node (ref "JP1") (pin "2") (pinfunction "2_2") (pintype "passive"))
      (node (ref "R10") (pin "1") (pinfunction "1_1") (pintype "passive"))
      (node (ref "S1") (pin "3") (pinfunction "3_3") (pintype "passive"))
      (node (ref "S1") (pin "4") (pinfunction "4_4") (pintype "passive"))
      (node (ref "U5") (pin "20") (pinfunction "/RESET_20") (pintype "bidirectional"))
    )
    (net (code "57") (name "/~{X-ENABLE}") (class "Default")
      (node (ref "P1") (pin "!EN") (pinfunction "~{ENABLE}_!EN") (pintype "input"))
      (node (ref "R17") (pin "2") (pinfunction "2_2") (pintype "passive"))
      (node (ref "U5") (pin "51") (pinfunction "PA0_AD0_51") (pintype "bidirectional"))
    )
    (net (code "58") (name "/~{Y-ENABLE}") (class "Default")
      (node (ref "P2") (pin "!EN") (pinfunction "~{ENABLE}_!EN") (pintype "input"))
      (node (ref "R16") (pin "2") (pinfunction "2_2") (pintype "passive"))
      (node (ref "U5") (pin "48") (pinfunction "PA3_AD3_48") (pintype "bidirectional"))
    )
    (net (code "59") (name "/~{Z-ENABLE}") (class "Default")
      (node (ref "P3") (pin "!EN") (pinfunction "~{ENABLE}_!EN") (pintype "input"))
      (node (ref "R18") (pin "2") (pinfunction "2_2") (pintype "passive"))
      (node (ref "U5") (pin "45") (pinfunction "PA6_AD6_45") (pintype "bidirectional"))
    )
    (net (code "60") (name "5V") (class "Default")
      (node (ref "C2") (pin "1") (pinfunction "1_1") (pintype "passive"))
      (node (ref "C5") (pin "2") (pinfunction "2_2") (pintype "passive"))
      (node (ref "C6") (pin "2") (pinfunction "2_2") (pintype "passive"))
      (node (ref "C7") (pin "1") (pinfunction "1_1") (pintype "passive"))
      (node (ref "C9") (pin "1") (pinfunction "1_1") (pintype "passive"))
      (node (ref "J16") (pin "2") (pinfunction "2_2") (pintype "passive"))
      (node (ref "JP1") (pin "5") (pinfunction "5_5") (pintype "passive"))
      (node (ref "JP6") (pin "3") (pinfunction "3_3") (pintype "passive"))
      (node (ref "JP7") (pin "2") (pinfunction "2_2") (pintype "passive"))
      (node (ref "L1") (pin "2") (pinfunction "2_2") (pintype "passive"))
      (node (ref "P1") (pin "VDD") (pinfunction "VDD_VDD") (pintype "power_in"))
      (node (ref "P2") (pin "VDD") (pinfunction "VDD_VDD") (pintype "power_in"))
      (node (ref "P3") (pin "VDD") (pinfunction "VDD_VDD") (pintype "power_in"))
      (node (ref "P4") (pin "VDD") (pinfunction "VDD_VDD") (pintype "power_in"))
      (node (ref "R1") (pin "2") (pinfunction "2_2") (pintype "passive"))
      (node (ref "R10") (pin "2") (pinfunction "2_2") (pintype "passive"))
      (node (ref "R11") (pin "2") (pinfunction "2_2") (pintype "passive"))
      (node (ref "R14") (pin "2") (pinfunction "2_2") (pintype "passive"))
      (node (ref "R15") (pin "2") (pinfunction "2_2") (pintype "passive"))
      (node (ref "R16") (pin "1") (pinfunction "1_1") (pintype "passive"))
      (node (ref "R17") (pin "1") (pinfunction "1_1") (pintype "passive"))
      (node (ref "R18") (pin "1") (pinfunction "1_1") (pintype "passive"))
      (node (ref "R19") (pin "1") (pinfunction "1_1") (pintype "passive"))
      (node (ref "R4") (pin "1") (pinfunction "1_1") (pintype "passive"))
      (node (ref "SJ1") (pin "2") (pinfunction "2_2") (pintype "passive"))
      (node (ref "SJ10") (pin "2") (pinfunction "2_2") (pintype "passive"))
      (node (ref "SJ11") (pin "2") (pinfunction "2_2") (pintype "passive"))
      (node (ref "SJ12") (pin "2") (pinfunction "2_2") (pintype "passive"))
      (node (ref "SJ13") (pin "2") (pinfunction "2_2") (pintype "passive"))
      (node (ref "SJ2") (pin "2") (pinfunction "2_2") (pintype "passive"))
      (node (ref "SJ3") (pin "2") (pinfunction "2_2") (pintype "passive"))
      (node (ref "SJ4") (pin "2") (pinfunction "2_2") (pintype "passive"))
      (node (ref "SJ5") (pin "2") (pinfunction "2_2") (pintype "passive"))
      (node (ref "SJ6") (pin "2") (pinfunction "2_2") (pintype "passive"))
      (node (ref "SJ7") (pin "2") (pinfunction "2_2") (pintype "passive"))
      (node (ref "SJ8") (pin "2") (pinfunction "2_2") (pintype "passive"))
      (node (ref "SJ9") (pin "2") (pinfunction "2_2") (pintype "passive"))
      (node (ref "U3") (pin "1") (pinfunction "IN_1") (pintype "power_in"))
      (node (ref "U4") (pin "14") (pinfunction "VCCB_14") (pintype "power_in"))
      (node (ref "U5") (pin "21") (pinfunction "VCC_21") (pintype "power_in"))
      (node (ref "U5") (pin "52") (pinfunction "VCC_52") (pintype "power_in"))
      (node (ref "U5") (pin "62") (pinfunction "AREF_62") (pintype "power_in"))
      (node (ref "U5") (pin "64") (pinfunction "AVCC_64") (pintype "power_in"))
    )
    (net (code "61") (name "12V") (class "Default")
      (node (ref "C1") (pin "1") (pinfunction "1_1") (pintype "passive"))
      (node (ref "C11") (pin "+") (pinfunction "+_+") (pintype "passive"))
      (node (ref "C14") (pin "+") (pinfunction "+_+") (pintype "passive"))
      (node (ref "C17") (pin "+") (pinfunction "+_+") (pintype "passive"))
      (node (ref "C18") (pin "+") (pinfunction "+_+") (pintype "passive"))
      (node (ref "C19") (pin "+") (pinfunction "+_+") (pintype "passive"))
      (node (ref "C20") (pin "+") (pinfunction "+_+") (pintype "passive"))
      (node (ref "F2") (pin "P$3") (pinfunction "P$3_P$3") (pintype "passive"))
      (node (ref "F2") (pin "P$4") (pinfunction "P$4_P$4") (pintype "passive"))
      (node (ref "J12") (pin "1") (pinfunction "1_1") (pintype "passive"))
      (node (ref "J14") (pin "3") (pinfunction "3_3") (pintype "power_in"))
      (node (ref "J14") (pin "4") (pinfunction "4_4") (pintype "power_in"))
      (node (ref "J16") (pin "3") (pinfunction "3_3") (pintype "passive"))
      (node (ref "J17") (pin "3") (pinfunction "3_3") (pintype "power_in"))
      (node (ref "J17") (pin "4") (pinfunction "4_4") (pintype "power_in"))
      (node (ref "J8") (pin "1") (pinfunction "1_1") (pintype "passive"))
      (node (ref "J9") (pin "1") (pinfunction "1_1") (pintype "passive"))
      (node (ref "JP6") (pin "1") (pinfunction "1_1") (pintype "passive"))
      (node (ref "JP7") (pin "4") (pinfunction "4_4") (pintype "passive"))
      (node (ref "P1") (pin "VMOT") (pinfunction "VMOT_VMOT") (pintype "power_in"))
      (node (ref "P2") (pin "VMOT") (pinfunction "VMOT_VMOT") (pintype "power_in"))
      (node (ref "P3") (pin "VMOT") (pinfunction "VMOT_VMOT") (pintype "power_in"))
      (node (ref "P4") (pin "VMOT") (pinfunction "VMOT_VMOT") (pintype "power_in"))
      (node (ref "U1") (pin "4") (pinfunction "~{SHDN}_4") (pintype "input"))
      (node (ref "U1") (pin "5") (pinfunction "VIN_5") (pintype "power_in"))
    )
    (net (code "62") (name "GND") (class "Default")
      (node (ref "C1") (pin "2") (pinfunction "2_2") (pintype "passive"))
      (node (ref "C10") (pin "2") (pinfunction "2_2") (pintype "passive"))
      (node (ref "C11") (pin "-") (pinfunction "-_-") (pintype "passive"))
      (node (ref "C12") (pin "1") (pinfunction "1_1") (pintype "passive"))
      (node (ref "C13") (pin "1") (pinfunction "1_1") (pintype "passive"))
      (node (ref "C14") (pin "-") (pinfunction "-_-") (pintype "passive"))
      (node (ref "C15") (pin "1") (pinfunction "1_1") (pintype "passive"))
      (node (ref "C16") (pin "1") (pinfunction "1_1") (pintype "passive"))
      (node (ref "C17") (pin "-") (pinfunction "-_-") (pintype "passive"))
      (node (ref "C18") (pin "-") (pinfunction "-_-") (pintype "passive"))
      (node (ref "C19") (pin "-") (pinfunction "-_-") (pintype "passive"))
      (node (ref "C2") (pin "2") (pinfunction "2_2") (pintype "passive"))
      (node (ref "C20") (pin "-") (pinfunction "-_-") (pintype "passive"))
      (node (ref "C4") (pin "1") (pinfunction "1_1") (pintype "passive"))
      (node (ref "C5") (pin "1") (pinfunction "1_1") (pintype "passive"))
      (node (ref "C6") (pin "1") (pinfunction "1_1") (pintype "passive"))
      (node (ref "C7") (pin "2") (pinfunction "2_2") (pintype "passive"))
      (node (ref "C8") (pin "1") (pinfunction "1_1") (pintype "passive"))
      (node (ref "C9") (pin "2") (pinfunction "2_2") (pintype "passive"))
      (node (ref "D1") (pin "A") (pinfunction "A_A") (pintype "passive"))
      (node (ref "D2") (pin "A") (pinfunction "A_A") (pintype "passive"))
      (node (ref "J1") (pin "1") (pinfunction "+_1") (pintype "passive"))
      (node (ref "J1") (pin "2") (pinfunction "-_2") (pintype "passive"))
      (node (ref "J10") (pin "6") (pinfunction "GND_6") (pintype "power_in"))
      (node (ref "J10") (pin "C1") (pinfunction "SHEILD_C1") (pintype "bidirectional"))
      (node (ref "J10") (pin "C2") (pinfunction "SHIELD_C2") (pintype "bidirectional"))
      (node (ref "J10") (pin "C3") (pinfunction "SHIELD_C3") (pintype "bidirectional"))
      (node (ref "J10") (pin "C4") (pinfunction "SHIELD_C4") (pintype "bidirectional"))
      (node (ref "J10") (pin "CD1") (pinfunction "CD1_CD1") (pintype "bidirectional"))
      (node (ref "J11") (pin "GND") (pinfunction "GND_GND") (pintype "bidirectional"))
      (node (ref "J11") (pin "GND1") (pinfunction "GND_GND1") (pintype "bidirectional"))
      (node (ref "J11") (pin "GND2") (pinfunction "GND_GND2") (pintype "bidirectional"))
      (node (ref "J11") (pin "GND3") (pinfunction "GND_GND3") (pintype "bidirectional"))
      (node (ref "J11") (pin "GND4") (pinfunction "GND_GND4") (pintype "bidirectional"))
      (node (ref "J11") (pin "GND5") (pinfunction "GND_GND5") (pintype "bidirectional"))
      (node (ref "J11") (pin "GND6") (pinfunction "GND_GND6") (pintype "bidirectional"))
      (node (ref "J11") (pin "GND7") (pinfunction "GND_GND7") (pintype "bidirectional"))
      (node (ref "J11") (pin "GND8") (pinfunction "GND_GND8") (pintype "bidirectional"))
      (node (ref "J13") (pin "3") (pinfunction "3_3") (pintype "power_in"))
      (node (ref "J13") (pin "4") (pinfunction "4_4") (pintype "power_in"))
      (node (ref "J15") (pin "4") (pinfunction "S_4") (pintype "passive"))
      (node (ref "J15") (pin "5") (pinfunction "S_5") (pintype "passive"))
      (node (ref "J15") (pin "6") (pinfunction "S_6") (pintype "passive"))
      (node (ref "J16") (pin "1") (pinfunction "1_1") (pintype "passive"))
      (node (ref "J18") (pin "2") (pinfunction "2_2") (pintype "passive"))
      (node (ref "J19") (pin "2") (pinfunction "2_2") (pintype "passive"))
      (node (ref "J2") (pin "1") (pinfunction "+_1") (pintype "passive"))
      (node (ref "J2") (pin "2") (pinfunction "-_2") (pintype "passive"))
      (node (ref "J3") (pin "1") (pinfunction "+_1") (pintype "passive"))
      (node (ref "J3") (pin "2") (pinfunction "-_2") (pintype "passive"))
      (node (ref "J4") (pin "1") (pinfunction "+_1") (pintype "passive"))
      (node (ref "J4") (pin "2") (pinfunction "-_2") (pintype "passive"))
      (node (ref "J5") (pin "1") (pinfunction "+_1") (pintype "passive"))
      (node (ref "J5") (pin "2") (pinfunction "-_2") (pintype "passive"))
      (node (ref "J6") (pin "1") (pinfunction "+_1") (pintype "passive"))
      (node (ref "J6") (pin "2") (pinfunction "-_2") (pintype "passive"))
      (node (ref "J7") (pin "1") (pinfunction "+_1") (pintype "passive"))
      (node (ref "J7") (pin "2") (pinfunction "-_2") (pintype "passive"))
      (node (ref "J8") (pin "2") (pinfunction "2_2") (pintype "passive"))
      (node (ref "J9") (pin "2") (pinfunction "2_2") (pintype "passive"))
      (node (ref "JP1") (pin "1") (pinfunction "1_1") (pintype "passive"))
      (node (ref "JP10") (pin "3") (pinfunction "3_3") (pintype "passive"))
      (node (ref "JP5") (pin "2") (pinfunction "2_2") (pintype "passive"))
      (node (ref "JP7") (pin "3") (pinfunction "3_3") (pintype "passive"))
      (node (ref "JP8") (pin "3") (pinfunction "3_3") (pintype "passive"))
      (node (ref "JP9") (pin "3") (pinfunction "3_3") (pintype "passive"))
      (node (ref "LED1") (pin "C") (pinfunction "C_C") (pintype "passive"))
      (node (ref "P1") (pin "GNDMOT") (pinfunction "GNDMOT_GNDMOT") (pintype "power_in"))
      (node (ref "P1") (pin "GNDVDD") (pinfunction "GNDVDD_GNDVDD") (pintype "power_in"))
      (node (ref "P2") (pin "GNDMOT") (pinfunction "GNDMOT_GNDMOT") (pintype "power_in"))
      (node (ref "P2") (pin "GNDVDD") (pinfunction "GNDVDD_GNDVDD") (pintype "power_in"))
      (node (ref "P3") (pin "GNDMOT") (pinfunction "GNDMOT_GNDMOT") (pintype "power_in"))
      (node (ref "P3") (pin "GNDVDD") (pinfunction "GNDVDD_GNDVDD") (pintype "power_in"))
      (node (ref "P4") (pin "GNDMOT") (pinfunction "GNDMOT_GNDMOT") (pintype "power_in"))
      (node (ref "P4") (pin "GNDVDD") (pinfunction "GNDVDD_GNDVDD") (pintype "power_in"))
      (node (ref "Q1") (pin "2") (pinfunction "S_2") (pintype "passive"))
      (node (ref "Q2") (pin "1") (pinfunction "S1_1") (pintype "passive"))
      (node (ref "Q2") (pin "2") (pinfunction "S2_2") (pintype "passive"))
      (node (ref "Q2") (pin "3") (pinfunction "S3_3") (pintype "passive"))
      (node (ref "Q3") (pin "2") (pinfunction "E_2") (pintype "passive"))
      (node (ref "Q4") (pin "1") (pinfunction "S1_1") (pintype "passive"))
      (node (ref "Q4") (pin "2") (pinfunction "S2_2") (pintype "passive"))
      (node (ref "Q4") (pin "3") (pinfunction "S3_3") (pintype "passive"))
      (node (ref "R12") (pin "2") (pinfunction "2_2") (pintype "passive"))
      (node (ref "R2") (pin "2") (pinfunction "2_2") (pintype "passive"))
      (node (ref "R5") (pin "2") (pinfunction "2_2") (pintype "passive"))
      (node (ref "R8") (pin "2") (pinfunction "2_2") (pintype "passive"))
      (node (ref "S1") (pin "1") (pinfunction "1_1") (pintype "passive"))
      (node (ref "S1") (pin "2") (pinfunction "2_2") (pintype "passive"))
      (node (ref "SCREW1") (pin "GND") (pinfunction "P$1_GND") (pintype "bidirectional"))
      (node (ref "SCREW2") (pin "GND") (pinfunction "P$1_GND") (pintype "bidirectional"))
      (node (ref "SCREW3") (pin "GND") (pinfunction "P$1_GND") (pintype "bidirectional"))
      (node (ref "SCREW4") (pin "GND") (pinfunction "P$1_GND") (pintype "bidirectional"))
      (node (ref "U1") (pin "2") (pinfunction "GND_2") (pintype "power_in"))
      (node (ref "U2") (pin "1") (pinfunction "GND_1") (pintype "power_in"))
      (node (ref "U3") (pin "3") (pinfunction "GND_3") (pintype "power_in"))
      (node (ref "U4") (pin "7") (pinfunction "GND_7") (pintype "power_in"))
      (node (ref "U5") (pin "22") (pinfunction "GND_22") (pintype "power_in"))
      (node (ref "U5") (pin "53") (pinfunction "GND_53") (pintype "power_in"))
      (node (ref "U5") (pin "6") (pinfunction "UGND_6") (pintype "power_in"))
      (node (ref "U5") (pin "63") (pinfunction "AGND_63") (pintype "power_in"))
    )
    (net (code "63") (name "Net-(F1-PadP$2)") (class "Default")
      (node (ref "F1") (pin "P$2") (pinfunction "P$2_P$2") (pintype "passive"))
      (node (ref "J12") (pin "2") (pinfunction "2_2") (pintype "passive"))
    )
    (net (code "64") (name "Net-(J15A-S)") (class "Default")
      (node (ref "F2") (pin "P$1") (pinfunction "P$1_P$1") (pintype "passive"))
      (node (ref "F2") (pin "P$2") (pinfunction "P$2_P$2") (pintype "passive"))
      (node (ref "J13") (pin "1") (pinfunction "1_1") (pintype "power_in"))
      (node (ref "J13") (pin "2") (pinfunction "2_2") (pintype "power_in"))
      (node (ref "J15") (pin "1") (pinfunction "S_1") (pintype "passive"))
      (node (ref "J15") (pin "2") (pinfunction "S_2") (pintype "passive"))
      (node (ref "J15") (pin "3") (pinfunction "S_3") (pintype "passive"))
    )
    (net (code "65") (name "Net-(JP10-Pad2)") (class "Default")
      (node (ref "JP10") (pin "2") (pinfunction "2_2") (pintype "passive"))
      (node (ref "JP6") (pin "2") (pinfunction "2_2") (pintype "passive"))
      (node (ref "JP8") (pin "2") (pinfunction "2_2") (pintype "passive"))
      (node (ref "JP9") (pin "2") (pinfunction "2_2") (pintype "passive"))
    )
    (net (code "66") (name "Net-(LED1-PadA)") (class "Default")
      (node (ref "LED1") (pin "A") (pinfunction "A_A") (pintype "passive"))
      (node (ref "R1") (pin "1") (pinfunction "1_1") (pintype "passive"))
    )
    (net (code "67") (name "Net-(P1-MOT-1A)") (class "Default")
      (node (ref "JP11") (pin "3") (pinfunction "3_3") (pintype "passive"))
      (node (ref "P1") (pin "1A") (pinfunction "MOT-1A_1A") (pintype "power_in"))
    )
    (net (code "68") (name "Net-(P1-MOT-1B)") (class "Default")
      (node (ref "JP11") (pin "4") (pinfunction "4_4") (pintype "passive"))
      (node (ref "P1") (pin "1B") (pinfunction "MOT-1B_1B") (pintype "power_in"))
    )
    (net (code "69") (name "Net-(P1-MOT-2A)") (class "Default")
      (node (ref "JP11") (pin "2") (pinfunction "2_2") (pintype "passive"))
      (node (ref "P1") (pin "2A") (pinfunction "MOT-2A_2A") (pintype "power_in"))
    )
    (net (code "70") (name "Net-(P1-MOT-2B)") (class "Default")
      (node (ref "JP11") (pin "1") (pinfunction "1_1") (pintype "passive"))
      (node (ref "P1") (pin "2B") (pinfunction "MOT-2B_2B") (pintype "power_in"))
    )
    (net (code "71") (name "Net-(P1-PadMS1)") (class "Default")
      (node (ref "P1") (pin "MS1") (pinfunction "MS1_MS1") (pintype "input"))
      (node (ref "SJ10") (pin "1") (pinfunction "1_1") (pintype "passive"))
    )
    (net (code "72") (name "Net-(P1-PadMS2)") (class "Default")
      (node (ref "P1") (pin "MS2") (pinfunction "MS2_MS2") (pintype "input"))
      (node (ref "SJ6") (pin "1") (pinfunction "1_1") (pintype "passive"))
    )
    (net (code "73") (name "Net-(P1-PadMS3)") (class "Default")
      (node (ref "P1") (pin "MS3") (pinfunction "MS3_MS3") (pintype "input"))
      (node (ref "SJ2") (pin "1") (pinfunction "1_1") (pintype "passive"))
    )
    (net (code "74") (name "Net-(P1-~{RESET})") (class "Default")
      (node (ref "P1") (pin "!RST") (pinfunction "~{RESET}_!RST") (pintype "input"))
      (node (ref "P1") (pin "!SLP") (pinfunction "~{SLEEP}_!SLP") (pintype "input"))
    )
    (net (code "75") (name "Net-(P2-MOT-1A)") (class "Default")
      (node (ref "JP12") (pin "3") (pinfunction "3_3") (pintype "passive"))
      (node (ref "P2") (pin "1A") (pinfunction "MOT-1A_1A") (pintype "power_in"))
    )
    (net (code "76") (name "Net-(P2-MOT-1B)") (class "Default")
      (node (ref "JP12") (pin "4") (pinfunction "4_4") (pintype "passive"))
      (node (ref "P2") (pin "1B") (pinfunction "MOT-1B_1B") (pintype "power_in"))
    )
    (net (code "77") (name "Net-(P2-MOT-2A)") (class "Default")
      (node (ref "JP12") (pin "2") (pinfunction "2_2") (pintype "passive"))
      (node (ref "P2") (pin "2A") (pinfunction "MOT-2A_2A") (pintype "power_in"))
    )
    (net (code "78") (name "Net-(P2-MOT-2B)") (class "Default")
      (node (ref "JP12") (pin "1") (pinfunction "1_1") (pintype "passive"))
      (node (ref "P2") (pin "2B") (pinfunction "MOT-2B_2B") (pintype "power_in"))
    )
    (net (code "79") (name "Net-(P2-PadMS1)") (class "Default")
      (node (ref "P2") (pin "MS1") (pinfunction "MS1_MS1") (pintype "input"))
      (node (ref "SJ11") (pin "1") (pinfunction "1_1") (pintype "passive"))
    )
    (net (code "80") (name "Net-(P2-PadMS2)") (class "Default")
      (node (ref "P2") (pin "MS2") (pinfunction "MS2_MS2") (pintype "input"))
      (node (ref "SJ7") (pin "1") (pinfunction "1_1") (pintype "passive"))
    )
    (net (code "81") (name "Net-(P2-PadMS3)") (class "Default")
      (node (ref "P2") (pin "MS3") (pinfunction "MS3_MS3") (pintype "input"))
      (node (ref "SJ3") (pin "1") (pinfunction "1_1") (pintype "passive"))
    )
    (net (code "82") (name "Net-(P2-~{RESET})") (class "Default")
      (node (ref "P2") (pin "!RST") (pinfunction "~{RESET}_!RST") (pintype "input"))
      (node (ref "P2") (pin "!SLP") (pinfunction "~{SLEEP}_!SLP") (pintype "input"))
    )
    (net (code "83") (name "Net-(P3-MOT-1A)") (class "Default")
      (node (ref "JP14") (pin "3") (pinfunction "3_3") (pintype "passive"))
      (node (ref "P3") (pin "1A") (pinfunction "MOT-1A_1A") (pintype "power_in"))
    )
    (net (code "84") (name "Net-(P3-MOT-1B)") (class "Default")
      (node (ref "JP14") (pin "4") (pinfunction "4_4") (pintype "passive"))
      (node (ref "P3") (pin "1B") (pinfunction "MOT-1B_1B") (pintype "power_in"))
    )
    (net (code "85") (name "Net-(P3-MOT-2A)") (class "Default")
      (node (ref "JP14") (pin "2") (pinfunction "2_2") (pintype "passive"))
      (node (ref "P3") (pin "2A") (pinfunction "MOT-2A_2A") (pintype "power_in"))
    )
    (net (code "86") (name "Net-(P3-MOT-2B)") (class "Default")
      (node (ref "JP14") (pin "1") (pinfunction "1_1") (pintype "passive"))
      (node (ref "P3") (pin "2B") (pinfunction "MOT-2B_2B") (pintype "power_in"))
    )
    (net (code "87") (name "Net-(P3-PadMS1)") (class "Default")
      (node (ref "P3") (pin "MS1") (pinfunction "MS1_MS1") (pintype "input"))
      (node (ref "SJ12") (pin "1") (pinfunction "1_1") (pintype "passive"))
    )
    (net (code "88") (name "Net-(P3-PadMS2)") (class "Default")
      (node (ref "P3") (pin "MS2") (pinfunction "MS2_MS2") (pintype "input"))
      (node (ref "SJ8") (pin "1") (pinfunction "1_1") (pintype "passive"))
    )
    (net (code "89") (name "Net-(P3-PadMS3)") (class "Default")
      (node (ref "P3") (pin "MS3") (pinfunction "MS3_MS3") (pintype "input"))
      (node (ref "SJ4") (pin "1") (pinfunction "1_1") (pintype "passive"))
    )
    (net (code "90") (name "Net-(P3-~{RESET})") (class "Default")
      (node (ref "P3") (pin "!RST") (pinfunction "~{RESET}_!RST") (pintype "input"))
      (node (ref "P3") (pin "!SLP") (pinfunction "~{SLEEP}_!SLP") (pintype "input"))
    )
    (net (code "91") (name "Net-(P4-MOT-1A)") (class "Default")
      (node (ref "JP13") (pin "3") (pinfunction "3_3") (pintype "passive"))
      (node (ref "P4") (pin "1A") (pinfunction "MOT-1A_1A") (pintype "power_in"))
    )
    (net (code "92") (name "Net-(P4-MOT-1B)") (class "Default")
      (node (ref "JP13") (pin "4") (pinfunction "4_4") (pintype "passive"))
      (node (ref "P4") (pin "1B") (pinfunction "MOT-1B_1B") (pintype "power_in"))
    )
    (net (code "93") (name "Net-(P4-MOT-2A)") (class "Default")
      (node (ref "JP13") (pin "2") (pinfunction "2_2") (pintype "passive"))
      (node (ref "P4") (pin "2A") (pinfunction "MOT-2A_2A") (pintype "power_in"))
    )
    (net (code "94") (name "Net-(P4-MOT-2B)") (class "Default")
      (node (ref "JP13") (pin "1") (pinfunction "1_1") (pintype "passive"))
      (node (ref "P4") (pin "2B") (pinfunction "MOT-2B_2B") (pintype "power_in"))
    )
    (net (code "95") (name "Net-(P4-PadMS1)") (class "Default")
      (node (ref "P4") (pin "MS1") (pinfunction "MS1_MS1") (pintype "input"))
      (node (ref "SJ13") (pin "1") (pinfunction "1_1") (pintype "passive"))
    )
    (net (code "96") (name "Net-(P4-PadMS2)") (class "Default")
      (node (ref "P4") (pin "MS2") (pinfunction "MS2_MS2") (pintype "input"))
      (node (ref "SJ9") (pin "1") (pinfunction "1_1") (pintype "passive"))
    )
    (net (code "97") (name "Net-(P4-PadMS3)") (class "Default")
      (node (ref "P4") (pin "MS3") (pinfunction "MS3_MS3") (pintype "input"))
      (node (ref "SJ5") (pin "1") (pinfunction "1_1") (pintype "passive"))
    )
    (net (code "98") (name "Net-(P4-~{RESET})") (class "Default")
      (node (ref "P4") (pin "!RST") (pinfunction "~{RESET}_!RST") (pintype "input"))
      (node (ref "P4") (pin "!SLP") (pinfunction "~{SLEEP}_!SLP") (pintype "input"))
    )
    (net (code "99") (name "Net-(Q1-D)") (class "Default")
      (node (ref "D1") (pin "C") (pinfunction "C_C") (pintype "passive"))
      (node (ref "F1") (pin "P$1") (pinfunction "P$1_P$1") (pintype "passive"))
      (node (ref "Q1") (pin "3") (pinfunction "D_3") (pintype "passive"))
    )
    (net (code "100") (name "Net-(Q1-G)") (class "Default")
      (node (ref "Q1") (pin "1") (pinfunction "G_1") (pintype "passive"))
      (node (ref "R3") (pin "2") (pinfunction "2_2") (pintype "passive"))
    )
    (net (code "101") (name "Net-(Q2-D)") (class "Default")
      (node (ref "J14") (pin "1") (pinfunction "1_1") (pintype "power_in"))
      (node (ref "J14") (pin "2") (pinfunction "2_2") (pintype "power_in"))
      (node (ref "Q2") (pin "5-8") (pinfunction "D_5-8") (pintype "passive"))
    )
    (net (code "102") (name "Net-(Q2-G)") (class "Default")
      (node (ref "Q2") (pin "4") (pinfunction "G_4") (pintype "passive"))
      (node (ref "R9") (pin "2") (pinfunction "2_2") (pintype "passive"))
    )
    (net (code "103") (name "Net-(Q3-B)") (class "Default")
      (node (ref "JP7") (pin "1") (pinfunction "1_1") (pintype "passive"))
      (node (ref "Q3") (pin "1") (pinfunction "B_1") (pintype "passive"))
    )
    (net (code "104") (name "Net-(Q4-D)") (class "Default")
      (node (ref "J17") (pin "1") (pinfunction "1_1") (pintype "power_in"))
      (node (ref "J17") (pin "2") (pinfunction "2_2") (pintype "power_in"))
      (node (ref "Q4") (pin "5-8") (pinfunction "D_5-8") (pintype "passive"))
    )
    (net (code "105") (name "Net-(Q4-G)") (class "Default")
      (node (ref "Q4") (pin "4") (pinfunction "G_4") (pintype "passive"))
      (node (ref "R13") (pin "2") (pinfunction "2_2") (pintype "passive"))
    )
    (net (code "106") (name "Net-(U1-CB)") (class "Default")
      (node (ref "C3") (pin "2") (pinfunction "2_2") (pintype "passive"))
      (node (ref "U1") (pin "1") (pinfunction "CB_1") (pintype "passive"))
    )
    (net (code "107") (name "Net-(U1-FB)") (class "Default")
      (node (ref "R4") (pin "2") (pinfunction "2_2") (pintype "passive"))
      (node (ref "R5") (pin "1") (pinfunction "1_1") (pintype "passive"))
      (node (ref "U1") (pin "3") (pinfunction "FB_3") (pintype "passive"))
    )
    (net (code "108") (name "Net-(U1-SW)") (class "Default")
      (node (ref "C3") (pin "1") (pinfunction "1_1") (pintype "passive"))
      (node (ref "D2") (pin "C") (pinfunction "C_C") (pintype "passive"))
      (node (ref "L1") (pin "1") (pinfunction "1_1") (pintype "passive"))
      (node (ref "U1") (pin "6") (pinfunction "SW_6") (pintype "passive"))
    )
    (net (code "109") (name "Net-(U5-D+)") (class "Default")
      (node (ref "R7") (pin "2") (pinfunction "2_2") (pintype "passive"))
      (node (ref "U5") (pin "5") (pinfunction "D+_5") (pintype "bidirectional"))
    )
    (net (code "110") (name "Net-(U5-D-)") (class "Default")
      (node (ref "R6") (pin "2") (pinfunction "2_2") (pintype "passive"))
      (node (ref "U5") (pin "4") (pinfunction "D-_4") (pintype "bidirectional"))
    )
    (net (code "111") (name "Net-(U5-UCAP)") (class "Default")
      (node (ref "C8") (pin "2") (pinfunction "2_2") (pintype "passive"))
      (node (ref "U5") (pin "7") (pinfunction "UCAP_7") (pintype "power_in"))
    )
    (net (code "112") (name "unconnected-(J10-DAT1-Pad8)") (class "Default")
      (node (ref "J10") (pin "8") (pinfunction "DAT1_8") (pintype "bidirectional"))
    )
    (net (code "113") (name "unconnected-(J10-DAT2-Pad1)") (class "Default")
      (node (ref "J10") (pin "1") (pinfunction "DAT2_1") (pintype "bidirectional"))
    )
  )
)
